# TOP.net
KiCad netlist of a schematic drawn in Altium Designer
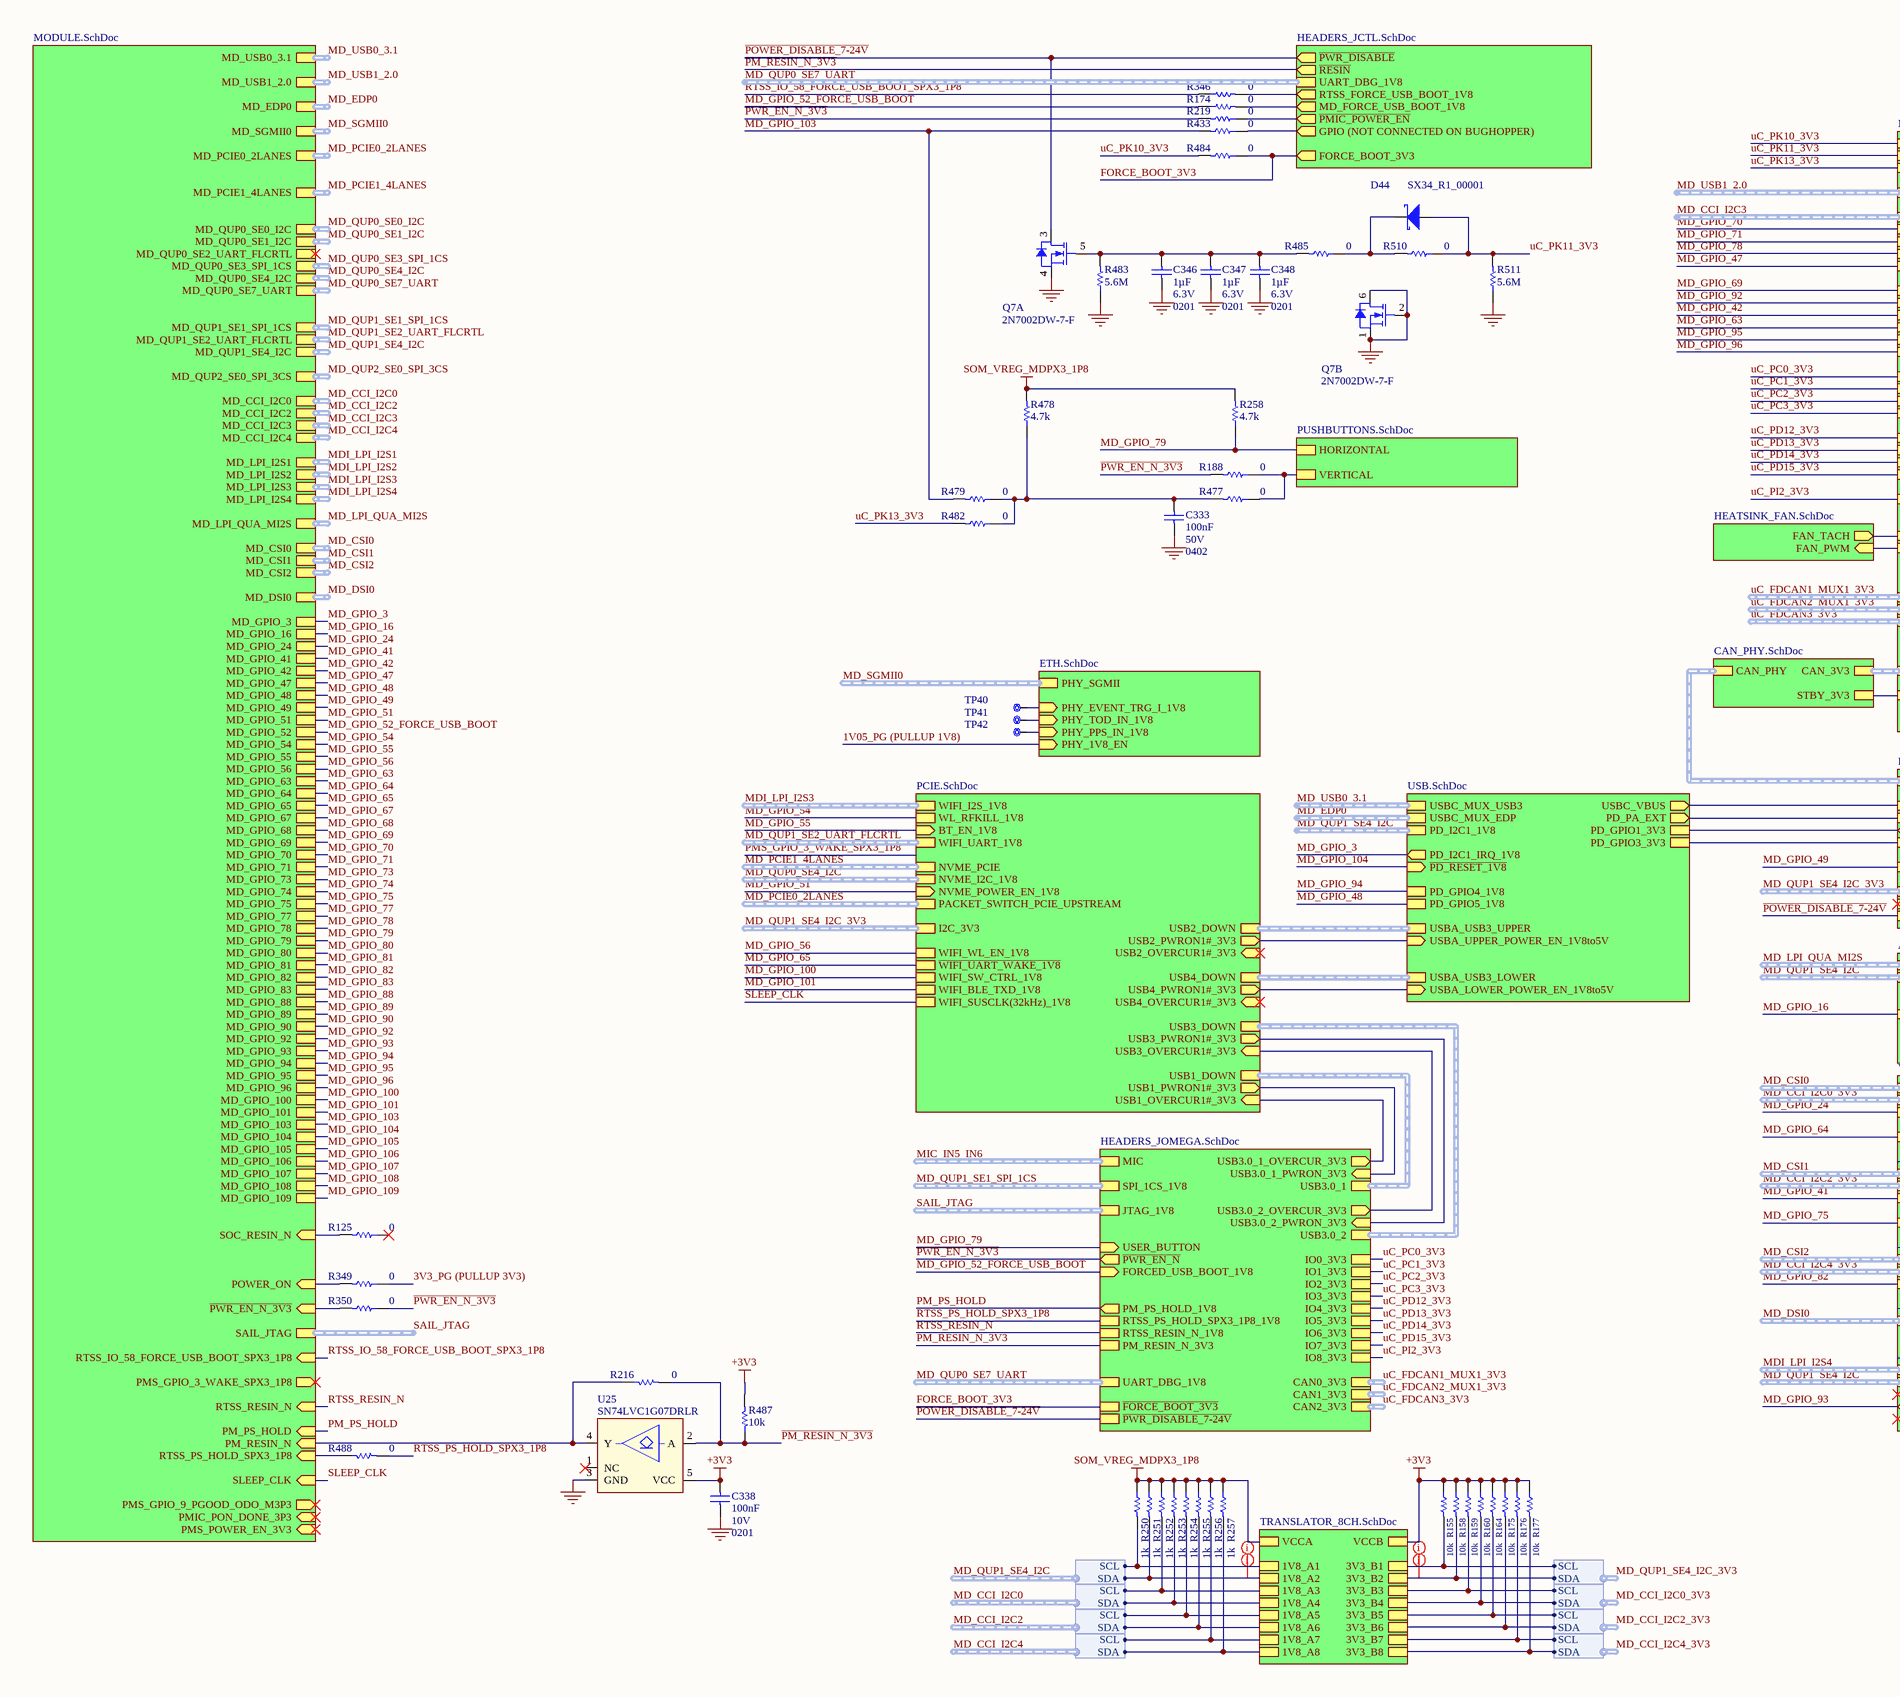
[diagram p0: TOP.SchDoc, left]
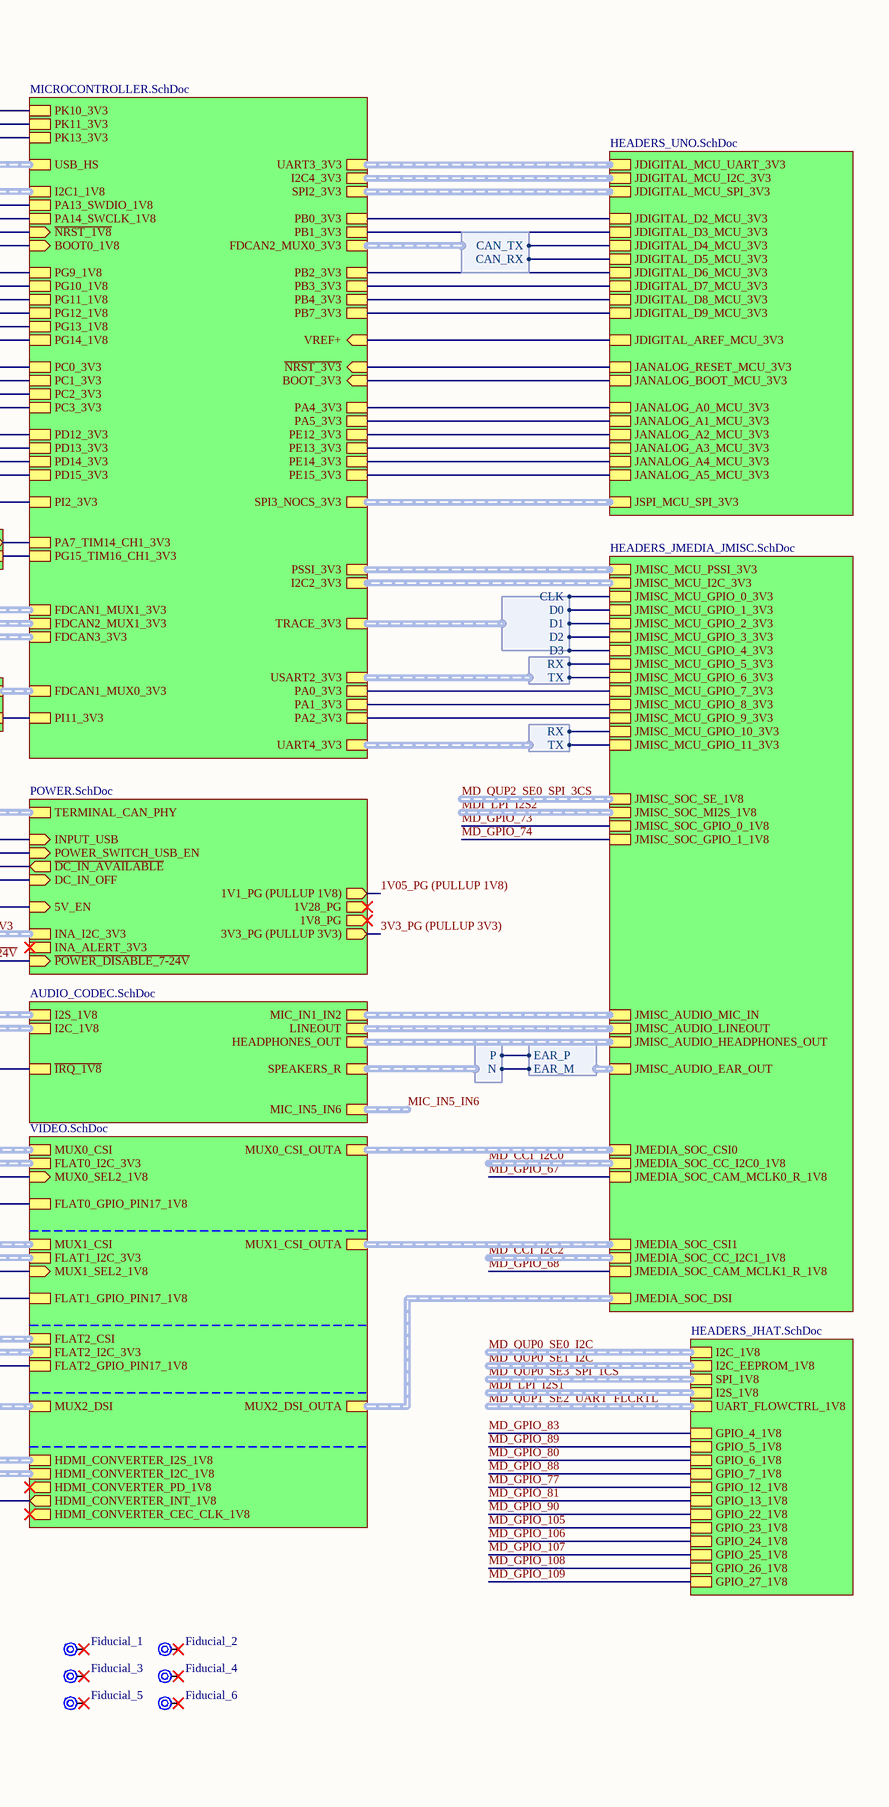
[diagram p1: TOP.SchDoc, right]

(export (version "E")
  (design (tool "Eeschema 10.0.6"))
  (components
    (comp (ref "C333")
      (value "100nF")
      (footprint "CAP-0402")
      (description "CAP CHIP 0402 100nF 10% 50V X5R")
      (fields
        (field (name "MANUFACTURER") "Murata")
        (field (name "PART NUMBER") "GRM155R61H104KE19D")
        (field (name "VOLTAGE") "50V")
        (field (name "CASE CODE (IMPERIAL)") "0402")
      )
      (libsource (lib "Clean") (part "CAP"))
    )
    (comp (ref "C338")
      (value "100nF")
      (footprint "CAP-0201")
      (description "CAP CHIP 0201 100nF 10% 10V X5R")
      (fields
        (field (name "PART NUMBER") "CL03A104KP3NNNC")
        (field (name "MANUFACTURER") "Samsung Electro-Mechanics")
        (field (name "VOLTAGE") "10V")
        (field (name "CASE CODE (IMPERIAL)") "0201")
      )
      (libsource (lib "Clean") (part "CAP"))
    )
    (comp (ref "C346")
      (value "1µF")
      (footprint "CAP-0201")
      (description "CAP CHIP 0201 1uF 20% 6.3V X5R")
      (fields
        (field (name "VOLTAGE") "6.3V")
        (field (name "TOLERANCE") "20%")
        (field (name "PART NUMBER") "GRM033R60J105MEA2D")
        (field (name "CASE CODE (IMPERIAL)") "0201")
      )
      (libsource (lib "Clean") (part "CAP"))
    )
    (comp (ref "C347")
      (value "1µF")
      (footprint "CAP-0201")
      (description "CAP CHIP 0201 1uF 20% 6.3V X5R")
      (fields
        (field (name "VOLTAGE") "6.3V")
        (field (name "TOLERANCE") "20%")
        (field (name "PART NUMBER") "GRM033R60J105MEA2D")
        (field (name "CASE CODE (IMPERIAL)") "0201")
      )
      (libsource (lib "Clean") (part "CAP"))
    )
    (comp (ref "C348")
      (value "1µF")
      (footprint "CAP-0201")
      (description "CAP CHIP 0201 1uF 20% 6.3V X5R")
      (fields
        (field (name "VOLTAGE") "6.3V")
        (field (name "TOLERANCE") "20%")
        (field (name "PART NUMBER") "GRM033R60J105MEA2D")
        (field (name "CASE CODE (IMPERIAL)") "0201")
      )
      (libsource (lib "Clean") (part "CAP"))
    )
    (comp (ref "D44")
      (value "SX34_R1_00001")
      (footprint "SMA DO214AC")
      (description "DIODE SCHOTTKY SMD 3A 40V SMA DO214AC")
      (fields (field (name "MANUFACTURER") "Panjit") (field (name "PART NUMBER") "SX34-AU_R1_000A1"))
      (libsource (lib "Clean") (part "Diode Schottky"))
    )
    (comp (ref "Fiducial_1")
      (value "Fiducial mark 1mm with 2mm solder")
      (footprint "Fiducial mark 1mm with circle-Footprint-1")
      (libsource (lib "Clean") (part "Fiducial mark 1mm with circle"))
    )
    (comp (ref "Fiducial_2")
      (value "Fiducial mark 1mm with 2mm solder")
      (footprint "Fiducial mark 1mm with circle-Footprint-1")
      (libsource (lib "Clean") (part "Fiducial mark 1mm with circle"))
    )
    (comp (ref "Fiducial_3")
      (value "Fiducial mark 1mm with 2mm solder")
      (footprint "Fiducial mark 1mm with circle-Footprint-1")
      (libsource (lib "Clean") (part "Fiducial mark 1mm with circle"))
    )
    (comp (ref "Fiducial_4")
      (value "Fiducial mark 1mm with 2mm solder")
      (footprint "Fiducial mark 1mm with circle-Footprint-1")
      (libsource (lib "Clean") (part "Fiducial mark 1mm with circle"))
    )
    (comp (ref "Fiducial_5")
      (value "Fiducial mark 1mm with 2mm solder")
      (footprint "Fiducial mark 1mm with circle-Footprint-1")
      (libsource (lib "Clean") (part "Fiducial mark 1mm with circle"))
    )
    (comp (ref "Fiducial_6")
      (value "Fiducial mark 1mm with 2mm solder")
      (footprint "Fiducial mark 1mm with circle-Footprint-1")
      (libsource (lib "Clean") (part "Fiducial mark 1mm with circle"))
    )
    (comp (ref "Q7")
      (value "2N7002DW-7-F")
      (footprint "SOT363")
      (description "MOSFET 2N-CH 60V 0.32A SOT363")
      (fields (field (name "MANUFACTURER") "Diodes Inc.") (field (name "PART NUMBER") "2N7002DW-7-F"))
      (libsource (lib "Clean") (part "2N7002DW-7-F"))
    )
    (comp (ref "R125")
      (value "0")
      (footprint "RES-0201")
      (description "RES CHIP 0201 0R")
      (fields (field (name "MANUFACTURER") "Vishay") (field (name "PART NUMBER") "CRCW02010000Z0ED"))
      (libsource (lib "Clean") (part "RES"))
    )
    (comp (ref "R155")
      (value "10k")
      (footprint "RES-0201")
      (description "RES CHIP 0201 10k 1% 1/20W")
      (fields (field (name "POWER") "50mW") (field (name "TOLERANCE") "1%"))
      (libsource (lib "Clean") (part "RES"))
    )
    (comp (ref "R158")
      (value "10k")
      (footprint "RES-0201")
      (description "RES CHIP 0201 10k 1% 1/20W")
      (fields (field (name "POWER") "50mW") (field (name "TOLERANCE") "1%"))
      (libsource (lib "Clean") (part "RES"))
    )
    (comp (ref "R159")
      (value "10k")
      (footprint "RES-0201")
      (description "RES CHIP 0201 10k 1% 1/20W")
      (fields (field (name "POWER") "50mW") (field (name "TOLERANCE") "1%"))
      (libsource (lib "Clean") (part "RES"))
    )
    (comp (ref "R160")
      (value "10k")
      (footprint "RES-0201")
      (description "RES CHIP 0201 10k 1% 1/20W")
      (fields (field (name "POWER") "50mW") (field (name "TOLERANCE") "1%"))
      (libsource (lib "Clean") (part "RES"))
    )
    (comp (ref "R164")
      (value "10k")
      (footprint "RES-0201")
      (description "RES CHIP 0201 10k 1% 1/20W")
      (fields (field (name "POWER") "50mW") (field (name "TOLERANCE") "1%"))
      (libsource (lib "Clean") (part "RES"))
    )
    (comp (ref "R174")
      (value "0")
      (footprint "RES-0201")
      (description "RES CHIP 0201 0R")
      (fields (field (name "MANUFACTURER") "Vishay") (field (name "PART NUMBER") "CRCW02010000Z0ED"))
      (libsource (lib "Clean") (part "RES"))
    )
    (comp (ref "R175")
      (value "10k")
      (footprint "RES-0201")
      (description "RES CHIP 0201 10k 1% 1/20W")
      (fields (field (name "POWER") "50mW") (field (name "TOLERANCE") "1%"))
      (libsource (lib "Clean") (part "RES"))
    )
    (comp (ref "R176")
      (value "10k")
      (footprint "RES-0201")
      (description "RES CHIP 0201 10k 1% 1/20W")
      (fields (field (name "POWER") "50mW") (field (name "TOLERANCE") "1%"))
      (libsource (lib "Clean") (part "RES"))
    )
    (comp (ref "R177")
      (value "10k")
      (footprint "RES-0201")
      (description "RES CHIP 0201 10k 1% 1/20W")
      (fields (field (name "POWER") "50mW") (field (name "TOLERANCE") "1%"))
      (libsource (lib "Clean") (part "RES"))
    )
    (comp (ref "R188")
      (value "0")
      (footprint "RES-0201")
      (description "RES CHIP 0201 0R")
      (fields (field (name "MANUFACTURER") "Vishay") (field (name "PART NUMBER") "CRCW02010000Z0ED"))
      (libsource (lib "Clean") (part "RES"))
    )
    (comp (ref "R216")
      (value "0")
      (footprint "RES-0201")
      (description "RES CHIP 0201 0R")
      (fields (field (name "MANUFACTURER") "Vishay") (field (name "PART NUMBER") "CRCW02010000Z0ED"))
      (libsource (lib "Clean") (part "RES"))
    )
    (comp (ref "R219")
      (value "0")
      (footprint "RES-0201")
      (description "RES CHIP 0201 0R")
      (fields (field (name "MANUFACTURER") "Vishay") (field (name "PART NUMBER") "CRCW02010000Z0ED"))
      (libsource (lib "Clean") (part "RES"))
    )
    (comp (ref "R250")
      (value "1k")
      (footprint "RES-0201")
      (description "RES CHIP 0201 1k 1% 1/20W")
      (fields (field (name "POWER") "50mW") (field (name "TOLERANCE") "1%"))
      (libsource (lib "Clean") (part "RES"))
    )
    (comp (ref "R251")
      (value "1k")
      (footprint "RES-0201")
      (description "RES CHIP 0201 1k 1% 1/20W")
      (fields (field (name "POWER") "50mW") (field (name "TOLERANCE") "1%"))
      (libsource (lib "Clean") (part "RES"))
    )
    (comp (ref "R252")
      (value "1k")
      (footprint "RES-0201")
      (description "RES CHIP 0201 1k 1% 1/20W")
      (fields (field (name "POWER") "50mW") (field (name "TOLERANCE") "1%"))
      (libsource (lib "Clean") (part "RES"))
    )
    (comp (ref "R253")
      (value "1k")
      (footprint "RES-0201")
      (description "RES CHIP 0201 1k 1% 1/20W")
      (fields (field (name "POWER") "50mW") (field (name "TOLERANCE") "1%"))
      (libsource (lib "Clean") (part "RES"))
    )
    (comp (ref "R254")
      (value "1k")
      (footprint "RES-0201")
      (description "RES CHIP 0201 1k 1% 1/20W")
      (fields (field (name "POWER") "50mW") (field (name "TOLERANCE") "1%"))
      (libsource (lib "Clean") (part "RES"))
    )
    (comp (ref "R255")
      (value "1k")
      (footprint "RES-0201")
      (description "RES CHIP 0201 1k 1% 1/20W")
      (fields (field (name "POWER") "50mW") (field (name "TOLERANCE") "1%"))
      (libsource (lib "Clean") (part "RES"))
    )
    (comp (ref "R256")
      (value "1k")
      (footprint "RES-0201")
      (description "RES CHIP 0201 1k 1% 1/20W")
      (fields (field (name "POWER") "50mW") (field (name "TOLERANCE") "1%"))
      (libsource (lib "Clean") (part "RES"))
    )
    (comp (ref "R257")
      (value "1k")
      (footprint "RES-0201")
      (description "RES CHIP 0201 1k 1% 1/20W")
      (fields (field (name "POWER") "50mW") (field (name "TOLERANCE") "1%"))
      (libsource (lib "Clean") (part "RES"))
    )
    (comp (ref "R258")
      (value "4.7k")
      (footprint "RES-0201")
      (description "RES CHIP 0201 4k7 1% 1/20W")
      (fields (field (name "POWER") "50mW") (field (name "TOLERANCE") "1%"))
      (libsource (lib "Clean") (part "RES"))
    )
    (comp (ref "R346")
      (value "0")
      (footprint "RES-0201")
      (description "RES CHIP 0201 0R")
      (fields (field (name "MANUFACTURER") "Vishay") (field (name "PART NUMBER") "CRCW02010000Z0ED"))
      (libsource (lib "Clean") (part "RES"))
    )
    (comp (ref "R349")
      (value "0")
      (footprint "RES-0201")
      (description "RES CHIP 0201 0R")
      (fields (field (name "MANUFACTURER") "Vishay") (field (name "PART NUMBER") "CRCW02010000Z0ED"))
      (libsource (lib "Clean") (part "RES"))
    )
    (comp (ref "R350")
      (value "0")
      (footprint "RES-0201")
      (description "RES CHIP 0201 0R")
      (fields (field (name "MANUFACTURER") "Vishay") (field (name "PART NUMBER") "CRCW02010000Z0ED"))
      (libsource (lib "Clean") (part "RES"))
    )
    (comp (ref "R433")
      (value "0")
      (footprint "RES-0201")
      (description "RES CHIP 0201 0R")
      (fields (field (name "MANUFACTURER") "Vishay") (field (name "PART NUMBER") "CRCW02010000Z0ED"))
      (libsource (lib "Clean") (part "RES"))
    )
    (comp (ref "R477")
      (value "0")
      (footprint "RES-0201")
      (description "RES CHIP 0201 0R")
      (fields (field (name "MANUFACTURER") "Vishay") (field (name "PART NUMBER") "CRCW02010000Z0ED"))
      (libsource (lib "Clean") (part "RES"))
    )
    (comp (ref "R478")
      (value "4.7k")
      (footprint "RES-0201")
      (description "RES CHIP 0201 4k7 1% 1/20W")
      (fields (field (name "POWER") "50mW") (field (name "TOLERANCE") "1%"))
      (libsource (lib "Clean") (part "RES"))
    )
    (comp (ref "R479")
      (value "0")
      (footprint "RES-0201")
      (description "RES CHIP 0201 0R")
      (fields (field (name "MANUFACTURER") "Vishay") (field (name "PART NUMBER") "CRCW02010000Z0ED"))
      (libsource (lib "Clean") (part "RES"))
    )
    (comp (ref "R482")
      (value "0")
      (footprint "RES-0201")
      (description "RES CHIP 0201 0R")
      (fields (field (name "MANUFACTURER") "Vishay") (field (name "PART NUMBER") "CRCW02010000Z0ED"))
      (libsource (lib "Clean") (part "RES"))
    )
    (comp (ref "R483")
      (value "5.6M")
      (footprint "RES-0201")
      (description "RES CHIP 0201 5.6M 1% 1/20W 200ppm")
      (fields (field (name "POWER") "50mW") (field (name "TOLERANCE") "1%"))
      (libsource (lib "Clean") (part "RES"))
    )
    (comp (ref "R484")
      (value "0")
      (footprint "RES-0201")
      (description "RES CHIP 0201 0R")
      (fields (field (name "MANUFACTURER") "Vishay") (field (name "PART NUMBER") "CRCW02010000Z0ED"))
      (libsource (lib "Clean") (part "RES"))
    )
    (comp (ref "R485")
      (value "0")
      (footprint "RES-0201")
      (description "RES CHIP 0201 0R")
      (fields (field (name "MANUFACTURER") "Vishay") (field (name "PART NUMBER") "CRCW02010000Z0ED"))
      (libsource (lib "Clean") (part "RES"))
    )
    (comp (ref "R487")
      (value "10k")
      (footprint "RES-0201")
      (description "RES CHIP 0201 10k 1% 1/20W")
      (fields (field (name "POWER") "50mW") (field (name "TOLERANCE") "1%"))
      (libsource (lib "Clean") (part "RES"))
    )
    (comp (ref "R488")
      (value "0")
      (footprint "RES-0201")
      (description "RES CHIP 0201 0R")
      (fields (field (name "MANUFACTURER") "Vishay") (field (name "PART NUMBER") "CRCW02010000Z0ED"))
      (libsource (lib "Clean") (part "RES"))
    )
    (comp (ref "R510")
      (value "0")
      (footprint "RES-0201")
      (description "RES CHIP 0201 0R")
      (fields (field (name "MANUFACTURER") "Vishay") (field (name "PART NUMBER") "CRCW02010000Z0ED"))
      (libsource (lib "Clean") (part "RES"))
    )
    (comp (ref "R511")
      (value "5.6M")
      (footprint "RES-0201")
      (description "RES CHIP 0201 5.6M 1% 1/20W 200ppm")
      (fields (field (name "PART NUMBER") "RC0201FR-075M6L") (field (name "TOLERANCE") "1%"))
      (libsource (lib "Clean") (part "RES"))
    )
    (comp (ref "TP40")
      (value "Test point 1.00mm")
      (footprint "TP-1.00MM")
      (fields (field (name "PART NUMBER") "This is not a component"))
      (libsource (lib "Clean") (part "TESTPOINT"))
    )
    (comp (ref "TP41")
      (value "Test point 1.00mm")
      (footprint "TP-1.00MM")
      (fields (field (name "PART NUMBER") "This is not a component"))
      (libsource (lib "Clean") (part "TESTPOINT"))
    )
    (comp (ref "TP42")
      (value "Test point 1.00mm")
      (footprint "TP-1.00MM")
      (fields (field (name "PART NUMBER") "This is not a component"))
      (libsource (lib "Clean") (part "TESTPOINT"))
    )
    (comp (ref "U25")
      (value "SN74LVC1G07DRLR")
      (footprint "TI DRL DRL0005A")
      (description "IC buffer open drain, 1.65V to 5.5V, 32mA sink current, SOT-5X3 1.6mmx1.6mm")
      (fields (field (name "MANUFACTURER") "Texas Instruments"))
      (libsource (lib "Clean") (part "SN74LVC1G07DRLR"))
    )
  )
  (nets
    (net (code "49") (name "+3V3") (class "Default")
      (node (ref "C338") (pin "2") (pinfunction "2_2") (pintype "passive"))
      (node (ref "R155") (pin "1") (pinfunction "1_1") (pintype "passive"))
      (node (ref "R158") (pin "1") (pinfunction "1_1") (pintype "passive"))
      (node (ref "R159") (pin "1") (pinfunction "1_1") (pintype "passive"))
      (node (ref "R160") (pin "1") (pinfunction "1_1") (pintype "passive"))
      (node (ref "R164") (pin "1") (pinfunction "1_1") (pintype "passive"))
      (node (ref "R175") (pin "1") (pinfunction "1_1") (pintype "passive"))
      (node (ref "R176") (pin "1") (pinfunction "1_1") (pintype "passive"))
      (node (ref "R177") (pin "1") (pinfunction "1_1") (pintype "passive"))
      (node (ref "R487") (pin "2") (pinfunction "2_2") (pintype "passive"))
      (node (ref "U25") (pin "5") (pinfunction "VCC_5") (pintype "passive"))
    )
    (net (code "51") (name "/1V8_A1") (class "Default")
      (node (ref "R250") (pin "2") (pinfunction "2_2") (pintype "passive"))
    )
    (net (code "52") (name "/1V8_A2") (class "Default")
      (node (ref "R251") (pin "2") (pinfunction "2_2") (pintype "passive"))
    )
    (net (code "53") (name "/1V8_A3") (class "Default")
      (node (ref "R252") (pin "2") (pinfunction "2_2") (pintype "passive"))
    )
    (net (code "54") (name "/1V8_A4") (class "Default")
      (node (ref "R253") (pin "2") (pinfunction "2_2") (pintype "passive"))
    )
    (net (code "55") (name "/1V8_A5") (class "Default")
      (node (ref "R254") (pin "2") (pinfunction "2_2") (pintype "passive"))
    )
    (net (code "56") (name "/1V8_A6") (class "Default")
      (node (ref "R255") (pin "2") (pinfunction "2_2") (pintype "passive"))
    )
    (net (code "57") (name "/1V8_A7") (class "Default")
      (node (ref "R256") (pin "2") (pinfunction "2_2") (pintype "passive"))
    )
    (net (code "58") (name "/1V8_A8") (class "Default")
      (node (ref "R257") (pin "2") (pinfunction "2_2") (pintype "passive"))
    )
    (net (code "61") (name "/3V3_B1") (class "Default")
      (node (ref "R155") (pin "2") (pinfunction "2_2") (pintype "passive"))
    )
    (net (code "62") (name "/3V3_B2") (class "Default")
      (node (ref "R158") (pin "2") (pinfunction "2_2") (pintype "passive"))
    )
    (net (code "63") (name "/3V3_B3") (class "Default")
      (node (ref "R159") (pin "2") (pinfunction "2_2") (pintype "passive"))
    )
    (net (code "64") (name "/3V3_B4") (class "Default")
      (node (ref "R160") (pin "2") (pinfunction "2_2") (pintype "passive"))
    )
    (net (code "65") (name "/3V3_B5") (class "Default")
      (node (ref "R164") (pin "2") (pinfunction "2_2") (pintype "passive"))
    )
    (net (code "66") (name "/3V3_B6") (class "Default")
      (node (ref "R175") (pin "2") (pinfunction "2_2") (pintype "passive"))
    )
    (net (code "67") (name "/3V3_B7") (class "Default")
      (node (ref "R176") (pin "2") (pinfunction "2_2") (pintype "passive"))
    )
    (net (code "68") (name "/3V3_B8") (class "Default")
      (node (ref "R177") (pin "2") (pinfunction "2_2") (pintype "passive"))
    )
    (net (code "69") (name "/3V3_PG (PULLUP 3V3)") (class "Default")
      (node (ref "R349") (pin "1") (pinfunction "1_1") (pintype "passive"))
    )
    (net (code "76") (name "/FORCE_BOOT_3V3") (class "Default")
      (node (ref "R484") (pin "1") (pinfunction "1_1") (pintype "passive"))
    )
    (net (code "77") (name "/GPIO (NOT CONNECTED ON BUGHOPPER)") (class "Default")
      (node (ref "R433") (pin "1") (pinfunction "1_1") (pintype "passive"))
    )
    (net (code "126") (name "/MD_FORCE_USB_BOOT_1V8") (class "Default")
      (node (ref "R174") (pin "2") (pinfunction "2_2") (pintype "passive"))
    )
    (net (code "136") (name "/MD_GPIO_52_FORCE_USB_BOOT") (class "Default")
      (node (ref "R174") (pin "1") (pinfunction "1_1") (pintype "passive"))
    )
    (net (code "153") (name "/MD_GPIO_79") (class "Default")
      (node (ref "R258") (pin "1") (pinfunction "1_1") (pintype "passive"))
    )
    (net (code "168") (name "/MD_GPIO_103") (class "Default")
      (node (ref "R433") (pin "2") (pinfunction "2_2") (pintype "passive"))
      (node (ref "R479") (pin "2") (pinfunction "2_2") (pintype "passive"))
    )
    (net (code "177") (name "/PHY_EVENT_TRG_I_1V8") (class "Default")
      (node (ref "TP40") (pin "X") (pinfunction "X_X") (pintype "passive"))
    )
    (net (code "178") (name "/PHY_PPS_IN_1V8") (class "Default")
      (node (ref "TP42") (pin "X") (pinfunction "X_X") (pintype "passive"))
    )
    (net (code "179") (name "/PHY_TOD_IN_1V8") (class "Default")
      (node (ref "TP41") (pin "X") (pinfunction "X_X") (pintype "passive"))
    )
    (net (code "187") (name "/PM_RESIN_N") (class "Default")
      (node (ref "R216") (pin "1") (pinfunction "1_1") (pintype "passive"))
      (node (ref "U25") (pin "4") (pinfunction "Y_4") (pintype "passive"))
    )
    (net (code "188") (name "/POWER_ON") (class "Default")
      (node (ref "R349") (pin "2") (pinfunction "2_2") (pintype "passive"))
    )
    (net (code "189") (name "/RTSS_FORCE_USB_BOOT_1V8") (class "Default")
      (node (ref "R346") (pin "2") (pinfunction "2_2") (pintype "passive"))
    )
    (net (code "190") (name "/RTSS_IO_58_FORCE_USB_BOOT_SPX3_1P8") (class "Default")
      (node (ref "R346") (pin "1") (pinfunction "1_1") (pintype "passive"))
    )
    (net (code "191") (name "/RTSS_PS_HOLD_SPX3_1P8") (class "Default")
      (node (ref "R488") (pin "2") (pinfunction "2_2") (pintype "passive"))
    )
    (net (code "192") (name "/RTSS_PS_HOLD_SPX3_1P8_1") (class "Default")
      (node (ref "R488") (pin "1") (pinfunction "1_1") (pintype "passive"))
    )
    (net (code "195") (name "/SOC_RESIN_N") (class "Default")
      (node (ref "R125") (pin "2") (pinfunction "2_2") (pintype "passive"))
    )
    (net (code "209") (name "/VERTICAL") (class "Default")
      (node (ref "R188") (pin "1") (pinfunction "1_1") (pintype "passive"))
      (node (ref "R477") (pin "1") (pinfunction "1_1") (pintype "passive"))
    )
    (net (code "219") (name "/uC_PK10_3V3") (class "Default")
      (node (ref "R484") (pin "2") (pinfunction "2_2") (pintype "passive"))
    )
    (net (code "220") (name "/uC_PK11_3V3") (class "Default")
      (node (ref "D44") (pin "A") (pinfunction "A_A") (pintype "passive"))
      (node (ref "R510") (pin "1") (pinfunction "1_1") (pintype "passive"))
      (node (ref "R511") (pin "2") (pinfunction "2_2") (pintype "passive"))
    )
    (net (code "221") (name "/uC_PK13_3V3") (class "Default")
      (node (ref "R482") (pin "2") (pinfunction "2_2") (pintype "passive"))
    )
    (net (code "265") (name "/~{PMIC_POWER_EN}") (class "Default")
      (node (ref "R219") (pin "1") (pinfunction "1_1") (pintype "passive"))
    )
    (net (code "266") (name "/~{PM_RESIN_N_3V3}") (class "Default")
      (node (ref "R216") (pin "2") (pinfunction "2_2") (pintype "passive"))
      (node (ref "R487") (pin "1") (pinfunction "1_1") (pintype "passive"))
      (node (ref "U25") (pin "2") (pinfunction "A_2") (pintype "passive"))
    )
    (net (code "267") (name "/~{POWER_DISABLE_7-24V}") (class "Default")
      (node (ref "Q7") (pin "3") (pinfunction "D_3") (pintype "passive"))
    )
    (net (code "268") (name "/~{PWR_EN_N_3V3}") (class "Default")
      (node (ref "R188") (pin "2") (pinfunction "2_2") (pintype "passive"))
      (node (ref "R219") (pin "2") (pinfunction "2_2") (pintype "passive"))
      (node (ref "R350") (pin "1") (pinfunction "1_1") (pintype "passive"))
    )
    (net (code "269") (name "/~{PWR_EN_N_3V3}_1") (class "Default")
      (node (ref "R350") (pin "2") (pinfunction "2_2") (pintype "passive"))
    )
    (net (code "270") (name "GND") (class "Default")
      (node (ref "C333") (pin "2") (pinfunction "2_2") (pintype "passive"))
      (node (ref "C338") (pin "1") (pinfunction "1_1") (pintype "passive"))
      (node (ref "C346") (pin "1") (pinfunction "1_1") (pintype "passive"))
      (node (ref "C347") (pin "1") (pinfunction "1_1") (pintype "passive"))
      (node (ref "C348") (pin "1") (pinfunction "1_1") (pintype "passive"))
      (node (ref "Q7") (pin "1") (pinfunction "S_1") (pintype "passive"))
      (node (ref "Q7") (pin "2") (pinfunction "G_2") (pintype "passive"))
      (node (ref "Q7") (pin "4") (pinfunction "S_4") (pintype "passive"))
      (node (ref "Q7") (pin "6") (pinfunction "D_6") (pintype "passive"))
      (node (ref "R483") (pin "1") (pinfunction "1_1") (pintype "passive"))
      (node (ref "R511") (pin "1") (pinfunction "1_1") (pintype "passive"))
      (node (ref "U25") (pin "3") (pinfunction "GND_3") (pintype "passive"))
    )
    (net (code "271") (name "Net-(C333-Pad1)") (class "Default")
      (node (ref "C333") (pin "1") (pinfunction "1_1") (pintype "passive"))
      (node (ref "R477") (pin "2") (pinfunction "2_2") (pintype "passive"))
      (node (ref "R478") (pin "1") (pinfunction "1_1") (pintype "passive"))
      (node (ref "R479") (pin "1") (pinfunction "1_1") (pintype "passive"))
      (node (ref "R482") (pin "1") (pinfunction "1_1") (pintype "passive"))
    )
    (net (code "272") (name "Net-(D44-PadC)") (class "Default")
      (node (ref "D44") (pin "C") (pinfunction "C_C") (pintype "passive"))
      (node (ref "R485") (pin "1") (pinfunction "1_1") (pintype "passive"))
      (node (ref "R510") (pin "2") (pinfunction "2_2") (pintype "passive"))
    )
    (net (code "273") (name "Net-(Q7A-G)") (class "Default")
      (node (ref "C346") (pin "2") (pinfunction "2_2") (pintype "passive"))
      (node (ref "C347") (pin "2") (pinfunction "2_2") (pintype "passive"))
      (node (ref "C348") (pin "2") (pinfunction "2_2") (pintype "passive"))
      (node (ref "Q7") (pin "5") (pinfunction "G_5") (pintype "passive"))
      (node (ref "R483") (pin "2") (pinfunction "2_2") (pintype "passive"))
      (node (ref "R485") (pin "2") (pinfunction "2_2") (pintype "passive"))
    )
    (net (code "274") (name "SOM_VREG_MDPX3_1P8") (class "Default")
      (node (ref "R250") (pin "1") (pinfunction "1_1") (pintype "passive"))
      (node (ref "R251") (pin "1") (pinfunction "1_1") (pintype "passive"))
      (node (ref "R252") (pin "1") (pinfunction "1_1") (pintype "passive"))
      (node (ref "R253") (pin "1") (pinfunction "1_1") (pintype "passive"))
      (node (ref "R254") (pin "1") (pinfunction "1_1") (pintype "passive"))
      (node (ref "R255") (pin "1") (pinfunction "1_1") (pintype "passive"))
      (node (ref "R256") (pin "1") (pinfunction "1_1") (pintype "passive"))
      (node (ref "R257") (pin "1") (pinfunction "1_1") (pintype "passive"))
      (node (ref "R258") (pin "2") (pinfunction "2_2") (pintype "passive"))
      (node (ref "R478") (pin "2") (pinfunction "2_2") (pintype "passive"))
    )
    (net (code "275") (name "unconnected-(Fiducial_1-Pad1)") (class "Default")
      (node (ref "Fiducial_1") (pin "1") (pinfunction "1_1") (pintype "passive+no_connect"))
    )
    (net (code "276") (name "unconnected-(Fiducial_2-Pad1)") (class "Default")
      (node (ref "Fiducial_2") (pin "1") (pinfunction "1_1") (pintype "passive+no_connect"))
    )
    (net (code "277") (name "unconnected-(Fiducial_3-Pad1)") (class "Default")
      (node (ref "Fiducial_3") (pin "1") (pinfunction "1_1") (pintype "passive+no_connect"))
    )
    (net (code "278") (name "unconnected-(Fiducial_4-Pad1)") (class "Default")
      (node (ref "Fiducial_4") (pin "1") (pinfunction "1_1") (pintype "passive+no_connect"))
    )
    (net (code "279") (name "unconnected-(Fiducial_5-Pad1)") (class "Default")
      (node (ref "Fiducial_5") (pin "1") (pinfunction "1_1") (pintype "passive+no_connect"))
    )
    (net (code "280") (name "unconnected-(Fiducial_6-Pad1)") (class "Default")
      (node (ref "Fiducial_6") (pin "1") (pinfunction "1_1") (pintype "passive+no_connect"))
    )
    (net (code "281") (name "unconnected-(R125-Pad1)") (class "Default")
      (node (ref "R125") (pin "1") (pinfunction "1_1") (pintype "passive+no_connect"))
    )
    (net (code "282") (name "unconnected-(U25-NC-Pad1)") (class "Default")
      (node (ref "U25") (pin "1") (pinfunction "NC_1") (pintype "passive+no_connect"))
    )
  )
)
